# SparkFun_Qwiic_Accelerometer_BMA400.net
KiCad netlist of a schematic drawn in EAGLE
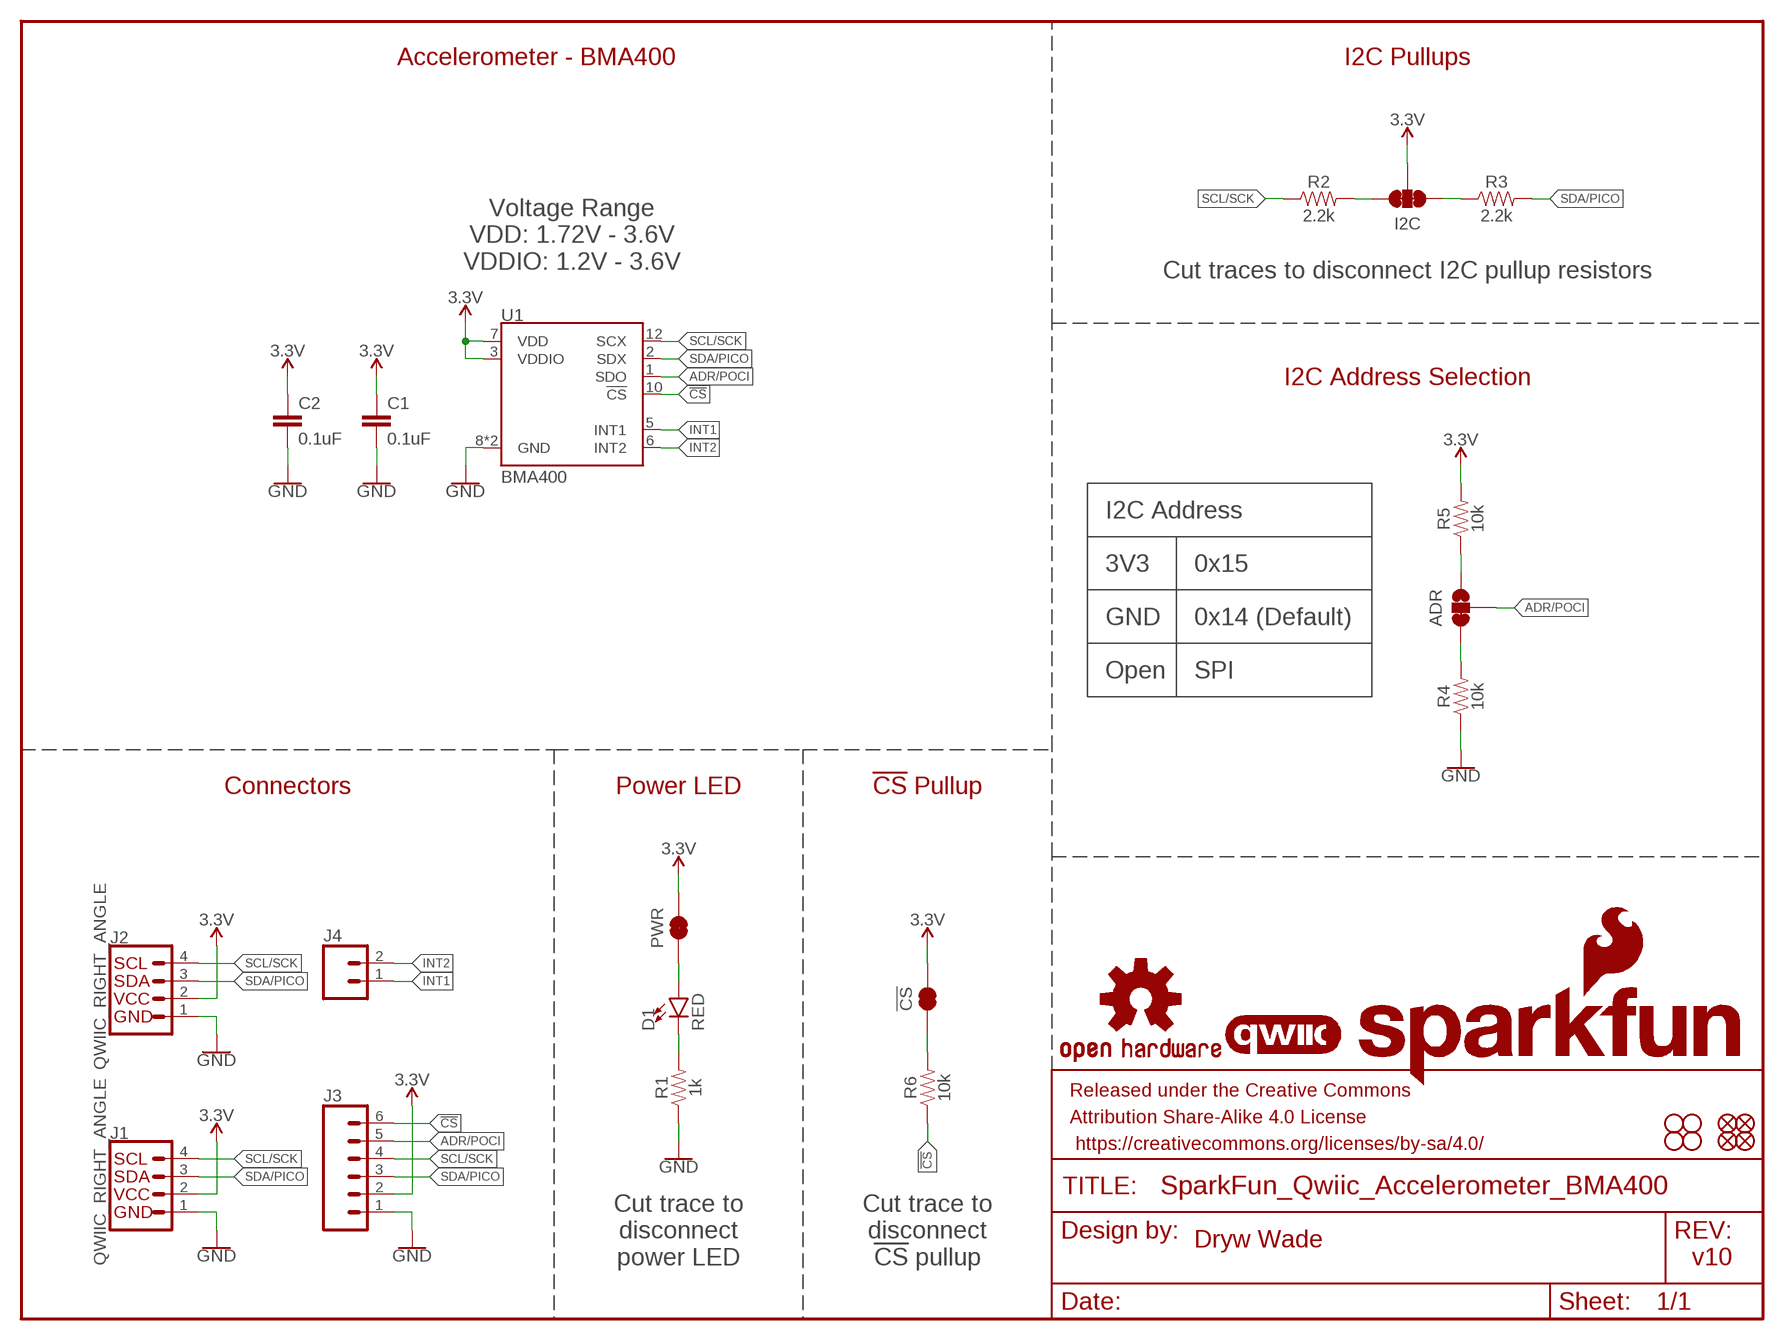
[diagram p0: schematic, sheet 1]

(export (version "E")
  (design (tool "Eeschema 10.0.6"))
  (components
    (comp (ref "!CS!")
      (value "JUMPER-SMT_2_NC_TRACE_SILK")
      (footprint "eagle-import:SMT-JUMPER_2_NC_TRACE_SILK")
      (libsource (lib "eagle-import") (part "JUMPER-SMT_2_NC_TRACE_SILK"))
    )
    (comp (ref "ADR")
      (value "JUMPER-SMT_3_1-NC_TRACE_SILK")
      (footprint "eagle-import:SMT-JUMPER_3_1-NC_TRACE_SILK")
      (libsource (lib "eagle-import") (part "JUMPER-SMT_3_1-NC_TRACE_SILK"))
    )
    (comp (ref "C1")
      (value "0.1uF")
      (footprint "eagle-import:0603")
      (libsource (lib "eagle-import") (part "0.1UF-0603-25V-(+80/-20%)"))
    )
    (comp (ref "C2")
      (value "0.1uF")
      (footprint "eagle-import:0603")
      (libsource (lib "eagle-import") (part "0.1UF-0603-25V-(+80/-20%)"))
    )
    (comp (ref "D1")
      (value "RED")
      (footprint "eagle-import:LED-0603")
      (libsource (lib "eagle-import") (part "LED-RED0603"))
    )
    (comp (ref "FD1")
      (value "FIDUCIAL1X2")
      (footprint "eagle-import:FIDUCIAL-1X2")
      (libsource (lib "eagle-import") (part "FIDUCIAL1X2"))
    )
    (comp (ref "FD2")
      (value "FIDUCIAL1X2")
      (footprint "eagle-import:FIDUCIAL-1X2")
      (libsource (lib "eagle-import") (part "FIDUCIAL1X2"))
    )
    (comp (ref "FD3")
      (value "FIDUCIAL1X2")
      (footprint "eagle-import:FIDUCIAL-1X2")
      (libsource (lib "eagle-import") (part "FIDUCIAL1X2"))
    )
    (comp (ref "FD4")
      (value "FIDUCIAL1X2")
      (footprint "eagle-import:FIDUCIAL-1X2")
      (libsource (lib "eagle-import") (part "FIDUCIAL1X2"))
    )
    (comp (ref "FRAME1")
      (value "FRAME-LETTER")
      (footprint "eagle-import:CREATIVE_COMMONS")
      (libsource (lib "eagle-import") (part "FRAME-LETTER"))
    )
    (comp (ref "H1")
      (value "STAND-OFF")
      (footprint "eagle-import:STAND-OFF")
      (libsource (lib "eagle-import") (part "STAND-OFF"))
    )
    (comp (ref "H2")
      (value "STAND-OFF")
      (footprint "eagle-import:STAND-OFF")
      (libsource (lib "eagle-import") (part "STAND-OFF"))
    )
    (comp (ref "H3")
      (value "STAND-OFF")
      (footprint "eagle-import:STAND-OFF")
      (libsource (lib "eagle-import") (part "STAND-OFF"))
    )
    (comp (ref "H4")
      (value "STAND-OFF")
      (footprint "eagle-import:STAND-OFF")
      (libsource (lib "eagle-import") (part "STAND-OFF"))
    )
    (comp (ref "I2C")
      (value "JUMPER-SMT_3_2-NC_TRACE_SILK")
      (footprint "eagle-import:SMT-JUMPER_3_2-NC_TRACE_SILK")
      (libsource (lib "eagle-import") (part "JUMPER-SMT_3_2-NC_TRACE_SILK"))
    )
    (comp (ref "J1")
      (value "QWIIC_RIGHT_ANGLE")
      (footprint "eagle-import:JST04_1MM_RA")
      (libsource (lib "eagle-import") (part "QWIIC_CONNECTORJS-1MM"))
    )
    (comp (ref "J2")
      (value "QWIIC_RIGHT_ANGLE")
      (footprint "eagle-import:JST04_1MM_RA")
      (libsource (lib "eagle-import") (part "QWIIC_CONNECTORJS-1MM"))
    )
    (comp (ref "J3")
      (value "CONN_06NO_SILK_NO_POP")
      (footprint "eagle-import:1X06_NO_SILK")
      (libsource (lib "eagle-import") (part "CONN_06NO_SILK_NO_POP"))
    )
    (comp (ref "J4")
      (value "CONN_021X02_NO_SILK")
      (footprint "eagle-import:1X02_NO_SILK")
      (libsource (lib "eagle-import") (part "CONN_021X02_NO_SILK"))
    )
    (comp (ref "LOGO1")
      (value "QWIIC_LOGO_5MM")
      (footprint "eagle-import:QWIIC_5MM")
      (libsource (lib "eagle-import") (part "QWIIC_LOGO_5MM"))
    )
    (comp (ref "LOGO2")
      (value "SFE_LOGO_NAME_FLAME.1_INCH")
      (footprint "eagle-import:SFE_LOGO_NAME_FLAME_.1")
      (libsource (lib "eagle-import") (part "SFE_LOGO_NAME_FLAME.1_INCH"))
    )
    (comp (ref "LOGO3")
      (value "OSHW-LOGOS")
      (footprint "eagle-import:OSHW-LOGO-S")
      (libsource (lib "eagle-import") (part "OSHW-LOGOS"))
    )
    (comp (ref "PWR")
      (value "JUMPER-SMT_2_NC_TRACE_SILK")
      (footprint "eagle-import:SMT-JUMPER_2_NC_TRACE_SILK")
      (libsource (lib "eagle-import") (part "JUMPER-SMT_2_NC_TRACE_SILK"))
    )
    (comp (ref "R1")
      (value "1k")
      (footprint "eagle-import:0603")
      (libsource (lib "eagle-import") (part "1KOHM-0603-1/10W-1%"))
    )
    (comp (ref "R2")
      (value "2.2k")
      (footprint "eagle-import:0603")
      (libsource (lib "eagle-import") (part "2.2KOHM-0603-1/10W-1%"))
    )
    (comp (ref "R3")
      (value "2.2k")
      (footprint "eagle-import:0603")
      (libsource (lib "eagle-import") (part "2.2KOHM-0603-1/10W-1%"))
    )
    (comp (ref "R4")
      (value "10k")
      (footprint "eagle-import:0603")
      (libsource (lib "eagle-import") (part "10KOHM-0603-1/10W-1%"))
    )
    (comp (ref "R5")
      (value "10k")
      (footprint "eagle-import:0603")
      (libsource (lib "eagle-import") (part "10KOHM-0603-1/10W-1%"))
    )
    (comp (ref "R6")
      (value "10k")
      (footprint "eagle-import:0603")
      (libsource (lib "eagle-import") (part "10KOHM-0603-1/10W-1%"))
    )
    (comp (ref "U1")
      (value "BMA400")
      (footprint "eagle-import:BMA400")
      (libsource (lib "eagle-import") (part "BMA400"))
    )
  )
  (nets
    (net (code "1") (name "/~{CS}") (class "Default")
      (node (ref "J3") (pin "6") (pinfunction "6_6") (pintype "passive"))
      (node (ref "R6") (pin "1") (pinfunction "1_1") (pintype "passive"))
      (node (ref "U1") (pin "10") (pinfunction "~{CS}_10") (pintype "input"))
    )
    (net (code "2") (name "3.3V") (class "Default")
      (node (ref "!CS!") (pin "2") (pinfunction "2_2") (pintype "passive"))
      (node (ref "C1") (pin "1") (pinfunction "1_1") (pintype "passive"))
      (node (ref "C2") (pin "1") (pinfunction "1_1") (pintype "passive"))
      (node (ref "I2C") (pin "2") (pinfunction "2_2") (pintype "passive"))
      (node (ref "J1") (pin "2") (pinfunction "2_2") (pintype "power_in"))
      (node (ref "J2") (pin "2") (pinfunction "2_2") (pintype "power_in"))
      (node (ref "J3") (pin "2") (pinfunction "2_2") (pintype "passive"))
      (node (ref "PWR") (pin "2") (pinfunction "2_2") (pintype "passive"))
      (node (ref "R5") (pin "2") (pinfunction "2_2") (pintype "passive"))
      (node (ref "U1") (pin "3") (pinfunction "VDDIO_3") (pintype "power_in"))
      (node (ref "U1") (pin "7") (pinfunction "VDD_7") (pintype "power_in"))
    )
    (net (code "3") (name "ADR{slash}POCI") (class "Default")
      (node (ref "ADR") (pin "2") (pinfunction "2_2") (pintype "passive"))
      (node (ref "J3") (pin "5") (pinfunction "5_5") (pintype "passive"))
      (node (ref "U1") (pin "1") (pinfunction "SDO_1") (pintype "output"))
    )
    (net (code "4") (name "GND") (class "Default")
      (node (ref "C1") (pin "2") (pinfunction "2_2") (pintype "passive"))
      (node (ref "C2") (pin "2") (pinfunction "2_2") (pintype "passive"))
      (node (ref "J1") (pin "1") (pinfunction "1_1") (pintype "power_in"))
      (node (ref "J2") (pin "1") (pinfunction "1_1") (pintype "power_in"))
      (node (ref "J3") (pin "1") (pinfunction "1_1") (pintype "passive"))
      (node (ref "R1") (pin "1") (pinfunction "1_1") (pintype "passive"))
      (node (ref "R4") (pin "1") (pinfunction "1_1") (pintype "passive"))
      (node (ref "U1") (pin "8") (pinfunction "GND_8") (pintype "power_in"))
      (node (ref "U1") (pin "9") (pinfunction "GND_9") (pintype "power_in"))
    )
    (net (code "5") (name "INT1") (class "Default")
      (node (ref "J4") (pin "1") (pinfunction "1_1") (pintype "passive"))
      (node (ref "U1") (pin "5") (pinfunction "INT1_5") (pintype "output"))
    )
    (net (code "6") (name "INT2") (class "Default")
      (node (ref "J4") (pin "2") (pinfunction "2_2") (pintype "passive"))
      (node (ref "U1") (pin "6") (pinfunction "INT2_6") (pintype "output"))
    )
    (net (code "7") (name "Net-(!CS!-Pad1)") (class "Default")
      (node (ref "!CS!") (pin "1") (pinfunction "1_1") (pintype "passive"))
      (node (ref "R6") (pin "2") (pinfunction "2_2") (pintype "passive"))
    )
    (net (code "8") (name "Net-(ADR-Pad1)") (class "Default")
      (node (ref "ADR") (pin "1") (pinfunction "1_1") (pintype "passive"))
      (node (ref "R5") (pin "1") (pinfunction "1_1") (pintype "passive"))
    )
    (net (code "9") (name "Net-(ADR-Pad3)") (class "Default")
      (node (ref "ADR") (pin "3") (pinfunction "3_3") (pintype "passive"))
      (node (ref "R4") (pin "2") (pinfunction "2_2") (pintype "passive"))
    )
    (net (code "10") (name "Net-(D1-PadA)") (class "Default")
      (node (ref "D1") (pin "A") (pinfunction "A_A") (pintype "passive"))
      (node (ref "PWR") (pin "1") (pinfunction "1_1") (pintype "passive"))
    )
    (net (code "11") (name "Net-(D1-PadC)") (class "Default")
      (node (ref "D1") (pin "C") (pinfunction "C_C") (pintype "passive"))
      (node (ref "R1") (pin "2") (pinfunction "2_2") (pintype "passive"))
    )
    (net (code "12") (name "Net-(I2C-Pad1)") (class "Default")
      (node (ref "I2C") (pin "1") (pinfunction "1_1") (pintype "passive"))
      (node (ref "R3") (pin "1") (pinfunction "1_1") (pintype "passive"))
    )
    (net (code "13") (name "Net-(I2C-Pad3)") (class "Default")
      (node (ref "I2C") (pin "3") (pinfunction "3_3") (pintype "passive"))
      (node (ref "R2") (pin "2") (pinfunction "2_2") (pintype "passive"))
    )
    (net (code "14") (name "SCL{slash}SCK") (class "Default")
      (node (ref "J1") (pin "4") (pinfunction "4_4") (pintype "passive"))
      (node (ref "J2") (pin "4") (pinfunction "4_4") (pintype "passive"))
      (node (ref "J3") (pin "4") (pinfunction "4_4") (pintype "passive"))
      (node (ref "R2") (pin "1") (pinfunction "1_1") (pintype "passive"))
      (node (ref "U1") (pin "12") (pinfunction "SCX_12") (pintype "input"))
    )
    (net (code "15") (name "SDA{slash}PICO") (class "Default")
      (node (ref "J1") (pin "3") (pinfunction "3_3") (pintype "passive"))
      (node (ref "J2") (pin "3") (pinfunction "3_3") (pintype "passive"))
      (node (ref "J3") (pin "3") (pinfunction "3_3") (pintype "passive"))
      (node (ref "R3") (pin "2") (pinfunction "2_2") (pintype "passive"))
      (node (ref "U1") (pin "2") (pinfunction "SDX_2") (pintype "bidirectional"))
    )
  )
)
